# SDRAM.net
KiCad netlist of a schematic drawn in Altium Designer
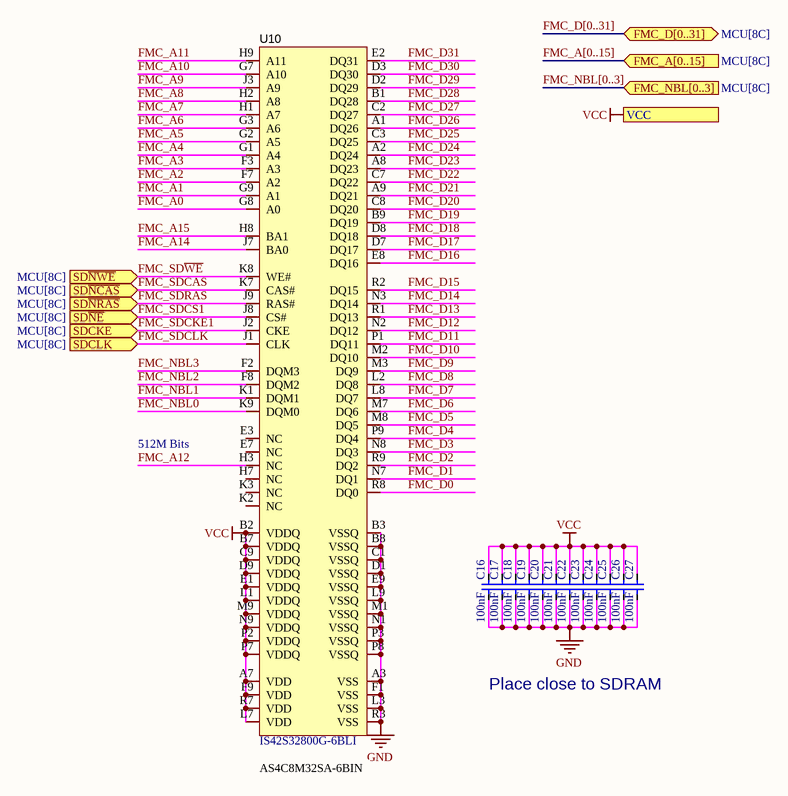
[diagram p0: SDRAM.SchDoc]

(export (version "E")
  (design (tool "Eeschema 10.0.6"))
  (components
    (comp (ref "C16")
      (value "100nF")
      (footprint "0402-C")
      (description "Capacitor")
      (libsource (lib "MyPcbLib") (part "电容-0402"))
    )
    (comp (ref "C17")
      (value "100nF")
      (footprint "0402-C")
      (description "Capacitor")
      (libsource (lib "MyPcbLib") (part "电容-0402"))
    )
    (comp (ref "C18")
      (value "100nF")
      (footprint "0402-C")
      (description "Capacitor")
      (libsource (lib "MyPcbLib") (part "电容-0402"))
    )
    (comp (ref "C19")
      (value "100nF")
      (footprint "0402-C")
      (description "Capacitor")
      (libsource (lib "MyPcbLib") (part "电容-0402"))
    )
    (comp (ref "C20")
      (value "100nF")
      (footprint "0402-C")
      (description "Capacitor")
      (libsource (lib "MyPcbLib") (part "电容-0402"))
    )
    (comp (ref "C21")
      (value "100nF")
      (footprint "0402-C")
      (description "Capacitor")
      (libsource (lib "MyPcbLib") (part "电容-0402"))
    )
    (comp (ref "C22")
      (value "100nF")
      (footprint "0402-C")
      (description "Capacitor")
      (libsource (lib "MyPcbLib") (part "电容-0402"))
    )
    (comp (ref "C23")
      (value "100nF")
      (footprint "0402-C")
      (description "Capacitor")
      (libsource (lib "MyPcbLib") (part "电容-0402"))
    )
    (comp (ref "C24")
      (value "100nF")
      (footprint "0402-C")
      (description "Capacitor")
      (libsource (lib "MyPcbLib") (part "电容-0402"))
    )
    (comp (ref "C25")
      (value "100nF")
      (footprint "0402-C")
      (description "Capacitor")
      (libsource (lib "MyPcbLib") (part "电容-0402"))
    )
    (comp (ref "C26")
      (value "100nF")
      (footprint "0402-C")
      (description "Capacitor")
      (libsource (lib "MyPcbLib") (part "电容-0402"))
    )
    (comp (ref "C27")
      (value "100nF")
      (footprint "0402-C")
      (description "Capacitor")
      (libsource (lib "MyPcbLib") (part "电容-0402"))
    )
    (comp (ref "U10")
      (value "IS42S32800G-6BLI")
      (footprint "BGA-90_L13.0-W8.0-R6-C15-P0.80-TL")
      (fields (field (name "MANUFACTURER") "ISSI(美国芯成)"))
      (libsource (lib "MyLib") (part "IS42S32800G-6BLI"))
    )
  )
  (nets
    (net (code "2") (name "/FMC_A0") (class "Default")
      (node (ref "U10") (pin "G8") (pinfunction "A0_G8") (pintype "passive"))
    )
    (net (code "3") (name "/FMC_A1") (class "Default")
      (node (ref "U10") (pin "G9") (pinfunction "A1_G9") (pintype "passive"))
    )
    (net (code "4") (name "/FMC_A2") (class "Default")
      (node (ref "U10") (pin "F7") (pinfunction "A2_F7") (pintype "passive"))
    )
    (net (code "5") (name "/FMC_A3") (class "Default")
      (node (ref "U10") (pin "F3") (pinfunction "A3_F3") (pintype "passive"))
    )
    (net (code "6") (name "/FMC_A4") (class "Default")
      (node (ref "U10") (pin "G1") (pinfunction "A4_G1") (pintype "passive"))
    )
    (net (code "7") (name "/FMC_A5") (class "Default")
      (node (ref "U10") (pin "G2") (pinfunction "A5_G2") (pintype "passive"))
    )
    (net (code "8") (name "/FMC_A6") (class "Default")
      (node (ref "U10") (pin "G3") (pinfunction "A6_G3") (pintype "passive"))
    )
    (net (code "9") (name "/FMC_A7") (class "Default")
      (node (ref "U10") (pin "H1") (pinfunction "A7_H1") (pintype "passive"))
    )
    (net (code "10") (name "/FMC_A8") (class "Default")
      (node (ref "U10") (pin "H2") (pinfunction "A8_H2") (pintype "passive"))
    )
    (net (code "11") (name "/FMC_A9") (class "Default")
      (node (ref "U10") (pin "J3") (pinfunction "A9_J3") (pintype "passive"))
    )
    (net (code "12") (name "/FMC_A10") (class "Default")
      (node (ref "U10") (pin "G7") (pinfunction "A10_G7") (pintype "passive"))
    )
    (net (code "13") (name "/FMC_A11") (class "Default")
      (node (ref "U10") (pin "H9") (pinfunction "A11_H9") (pintype "passive"))
    )
    (net (code "14") (name "/FMC_A12") (class "Default")
      (node (ref "U10") (pin "H3") (pinfunction "NC_H3") (pintype "passive"))
    )
    (net (code "15") (name "/FMC_A14") (class "Default")
      (node (ref "U10") (pin "J7") (pinfunction "BA0_J7") (pintype "passive"))
    )
    (net (code "16") (name "/FMC_A15") (class "Default")
      (node (ref "U10") (pin "H8") (pinfunction "BA1_H8") (pintype "passive"))
    )
    (net (code "18") (name "/FMC_D0") (class "Default")
      (node (ref "U10") (pin "R8") (pinfunction "DQ0_R8") (pintype "passive"))
    )
    (net (code "19") (name "/FMC_D1") (class "Default")
      (node (ref "U10") (pin "N7") (pinfunction "DQ1_N7") (pintype "passive"))
    )
    (net (code "20") (name "/FMC_D2") (class "Default")
      (node (ref "U10") (pin "R9") (pinfunction "DQ2_R9") (pintype "passive"))
    )
    (net (code "21") (name "/FMC_D3") (class "Default")
      (node (ref "U10") (pin "N8") (pinfunction "DQ3_N8") (pintype "passive"))
    )
    (net (code "22") (name "/FMC_D4") (class "Default")
      (node (ref "U10") (pin "P9") (pinfunction "DQ4_P9") (pintype "passive"))
    )
    (net (code "23") (name "/FMC_D5") (class "Default")
      (node (ref "U10") (pin "M8") (pinfunction "DQ5_M8") (pintype "passive"))
    )
    (net (code "24") (name "/FMC_D6") (class "Default")
      (node (ref "U10") (pin "M7") (pinfunction "DQ6_M7") (pintype "passive"))
    )
    (net (code "25") (name "/FMC_D7") (class "Default")
      (node (ref "U10") (pin "L8") (pinfunction "DQ7_L8") (pintype "passive"))
    )
    (net (code "26") (name "/FMC_D8") (class "Default")
      (node (ref "U10") (pin "L2") (pinfunction "DQ8_L2") (pintype "passive"))
    )
    (net (code "27") (name "/FMC_D9") (class "Default")
      (node (ref "U10") (pin "M3") (pinfunction "DQ9_M3") (pintype "passive"))
    )
    (net (code "28") (name "/FMC_D10") (class "Default")
      (node (ref "U10") (pin "M2") (pinfunction "DQ10_M2") (pintype "passive"))
    )
    (net (code "29") (name "/FMC_D11") (class "Default")
      (node (ref "U10") (pin "P1") (pinfunction "DQ11_P1") (pintype "passive"))
    )
    (net (code "30") (name "/FMC_D12") (class "Default")
      (node (ref "U10") (pin "N2") (pinfunction "DQ12_N2") (pintype "passive"))
    )
    (net (code "31") (name "/FMC_D13") (class "Default")
      (node (ref "U10") (pin "R1") (pinfunction "DQ13_R1") (pintype "passive"))
    )
    (net (code "32") (name "/FMC_D14") (class "Default")
      (node (ref "U10") (pin "N3") (pinfunction "DQ14_N3") (pintype "passive"))
    )
    (net (code "33") (name "/FMC_D15") (class "Default")
      (node (ref "U10") (pin "R2") (pinfunction "DQ15_R2") (pintype "passive"))
    )
    (net (code "34") (name "/FMC_D16") (class "Default")
      (node (ref "U10") (pin "E8") (pinfunction "DQ16_E8") (pintype "passive"))
    )
    (net (code "35") (name "/FMC_D17") (class "Default")
      (node (ref "U10") (pin "D7") (pinfunction "DQ17_D7") (pintype "passive"))
    )
    (net (code "36") (name "/FMC_D18") (class "Default")
      (node (ref "U10") (pin "D8") (pinfunction "DQ18_D8") (pintype "passive"))
    )
    (net (code "37") (name "/FMC_D19") (class "Default")
      (node (ref "U10") (pin "B9") (pinfunction "DQ19_B9") (pintype "passive"))
    )
    (net (code "38") (name "/FMC_D20") (class "Default")
      (node (ref "U10") (pin "C8") (pinfunction "DQ20_C8") (pintype "passive"))
    )
    (net (code "39") (name "/FMC_D21") (class "Default")
      (node (ref "U10") (pin "A9") (pinfunction "DQ21_A9") (pintype "passive"))
    )
    (net (code "40") (name "/FMC_D22") (class "Default")
      (node (ref "U10") (pin "C7") (pinfunction "DQ22_C7") (pintype "passive"))
    )
    (net (code "41") (name "/FMC_D23") (class "Default")
      (node (ref "U10") (pin "A8") (pinfunction "DQ23_A8") (pintype "passive"))
    )
    (net (code "42") (name "/FMC_D24") (class "Default")
      (node (ref "U10") (pin "A2") (pinfunction "DQ24_A2") (pintype "passive"))
    )
    (net (code "43") (name "/FMC_D25") (class "Default")
      (node (ref "U10") (pin "C3") (pinfunction "DQ25_C3") (pintype "passive"))
    )
    (net (code "44") (name "/FMC_D26") (class "Default")
      (node (ref "U10") (pin "A1") (pinfunction "DQ26_A1") (pintype "passive"))
    )
    (net (code "45") (name "/FMC_D27") (class "Default")
      (node (ref "U10") (pin "C2") (pinfunction "DQ27_C2") (pintype "passive"))
    )
    (net (code "46") (name "/FMC_D28") (class "Default")
      (node (ref "U10") (pin "B1") (pinfunction "DQ28_B1") (pintype "passive"))
    )
    (net (code "47") (name "/FMC_D29") (class "Default")
      (node (ref "U10") (pin "D2") (pinfunction "DQ29_D2") (pintype "passive"))
    )
    (net (code "48") (name "/FMC_D30") (class "Default")
      (node (ref "U10") (pin "D3") (pinfunction "DQ30_D3") (pintype "passive"))
    )
    (net (code "49") (name "/FMC_D31") (class "Default")
      (node (ref "U10") (pin "E2") (pinfunction "DQ31_E2") (pintype "passive"))
    )
    (net (code "51") (name "/FMC_NBL0") (class "Default")
      (node (ref "U10") (pin "K9") (pinfunction "DQM0_K9") (pintype "passive"))
    )
    (net (code "52") (name "/FMC_NBL1") (class "Default")
      (node (ref "U10") (pin "K1") (pinfunction "DQM1_K1") (pintype "passive"))
    )
    (net (code "53") (name "/FMC_NBL2") (class "Default")
      (node (ref "U10") (pin "F8") (pinfunction "DQM2_F8") (pintype "passive"))
    )
    (net (code "54") (name "/FMC_NBL3") (class "Default")
      (node (ref "U10") (pin "F2") (pinfunction "DQM3_F2") (pintype "passive"))
    )
    (net (code "56") (name "/FMC_SDCKE1") (class "Default")
      (node (ref "U10") (pin "J2") (pinfunction "CKE_J2") (pintype "passive"))
    )
    (net (code "57") (name "/FMC_SDCLK") (class "Default")
      (node (ref "U10") (pin "J1") (pinfunction "CLK_J1") (pintype "passive"))
    )
    (net (code "58") (name "/FMC_SD~{CAS}") (class "Default")
      (node (ref "U10") (pin "K7") (pinfunction "CAS#_K7") (pintype "passive"))
    )
    (net (code "59") (name "/FMC_SD~{CS}1") (class "Default")
      (node (ref "U10") (pin "J8") (pinfunction "CS#_J8") (pintype "passive"))
    )
    (net (code "60") (name "/FMC_SD~{RAS}") (class "Default")
      (node (ref "U10") (pin "J9") (pinfunction "RAS#_J9") (pintype "passive"))
    )
    (net (code "61") (name "/FMC_SD~{WE}") (class "Default")
      (node (ref "U10") (pin "K8") (pinfunction "WE#_K8") (pintype "passive"))
    )
    (net (code "62") (name "GND") (class "Default")
      (node (ref "C16") (pin "2") (pinfunction "2_2") (pintype "passive"))
      (node (ref "C17") (pin "2") (pinfunction "2_2") (pintype "passive"))
      (node (ref "C18") (pin "2") (pinfunction "2_2") (pintype "passive"))
      (node (ref "C19") (pin "2") (pinfunction "2_2") (pintype "passive"))
      (node (ref "C20") (pin "2") (pinfunction "2_2") (pintype "passive"))
      (node (ref "C21") (pin "2") (pinfunction "2_2") (pintype "passive"))
      (node (ref "C22") (pin "2") (pinfunction "2_2") (pintype "passive"))
      (node (ref "C23") (pin "2") (pinfunction "2_2") (pintype "passive"))
      (node (ref "C24") (pin "2") (pinfunction "2_2") (pintype "passive"))
      (node (ref "C25") (pin "2") (pinfunction "2_2") (pintype "passive"))
      (node (ref "C26") (pin "2") (pinfunction "2_2") (pintype "passive"))
      (node (ref "C27") (pin "2") (pinfunction "2_2") (pintype "passive"))
      (node (ref "U10") (pin "A3") (pinfunction "VSS_A3") (pintype "passive"))
      (node (ref "U10") (pin "B3") (pinfunction "VSSQ_B3") (pintype "passive"))
      (node (ref "U10") (pin "B8") (pinfunction "VSSQ_B8") (pintype "passive"))
      (node (ref "U10") (pin "C1") (pinfunction "VSSQ_C1") (pintype "passive"))
      (node (ref "U10") (pin "D1") (pinfunction "VSSQ_D1") (pintype "passive"))
      (node (ref "U10") (pin "E9") (pinfunction "VSSQ_E9") (pintype "passive"))
      (node (ref "U10") (pin "F1") (pinfunction "VSS_F1") (pintype "passive"))
      (node (ref "U10") (pin "L3") (pinfunction "VSS_L3") (pintype "passive"))
      (node (ref "U10") (pin "L9") (pinfunction "VSSQ_L9") (pintype "passive"))
      (node (ref "U10") (pin "M1") (pinfunction "VSSQ_M1") (pintype "passive"))
      (node (ref "U10") (pin "N1") (pinfunction "VSSQ_N1") (pintype "passive"))
      (node (ref "U10") (pin "P3") (pinfunction "VSSQ_P3") (pintype "passive"))
      (node (ref "U10") (pin "P8") (pinfunction "VSSQ_P8") (pintype "passive"))
      (node (ref "U10") (pin "R3") (pinfunction "VSS_R3") (pintype "passive"))
    )
    (net (code "63") (name "VCC") (class "Default")
      (node (ref "C16") (pin "1") (pinfunction "1_1") (pintype "passive"))
      (node (ref "C17") (pin "1") (pinfunction "1_1") (pintype "passive"))
      (node (ref "C18") (pin "1") (pinfunction "1_1") (pintype "passive"))
      (node (ref "C19") (pin "1") (pinfunction "1_1") (pintype "passive"))
      (node (ref "C20") (pin "1") (pinfunction "1_1") (pintype "passive"))
      (node (ref "C21") (pin "1") (pinfunction "1_1") (pintype "passive"))
      (node (ref "C22") (pin "1") (pinfunction "1_1") (pintype "passive"))
      (node (ref "C23") (pin "1") (pinfunction "1_1") (pintype "passive"))
      (node (ref "C24") (pin "1") (pinfunction "1_1") (pintype "passive"))
      (node (ref "C25") (pin "1") (pinfunction "1_1") (pintype "passive"))
      (node (ref "C26") (pin "1") (pinfunction "1_1") (pintype "passive"))
      (node (ref "C27") (pin "1") (pinfunction "1_1") (pintype "passive"))
      (node (ref "U10") (pin "A7") (pinfunction "VDD_A7") (pintype "passive"))
      (node (ref "U10") (pin "B2") (pinfunction "VDDQ_B2") (pintype "passive"))
      (node (ref "U10") (pin "B7") (pinfunction "VDDQ_B7") (pintype "passive"))
      (node (ref "U10") (pin "C9") (pinfunction "VDDQ_C9") (pintype "passive"))
      (node (ref "U10") (pin "D9") (pinfunction "VDDQ_D9") (pintype "passive"))
      (node (ref "U10") (pin "E1") (pinfunction "VDDQ_E1") (pintype "passive"))
      (node (ref "U10") (pin "F9") (pinfunction "VDD_F9") (pintype "passive"))
      (node (ref "U10") (pin "L1") (pinfunction "VDDQ_L1") (pintype "passive"))
      (node (ref "U10") (pin "L7") (pinfunction "VDD_L7") (pintype "passive"))
      (node (ref "U10") (pin "M9") (pinfunction "VDDQ_M9") (pintype "passive"))
      (node (ref "U10") (pin "N9") (pinfunction "VDDQ_N9") (pintype "passive"))
      (node (ref "U10") (pin "P2") (pinfunction "VDDQ_P2") (pintype "passive"))
      (node (ref "U10") (pin "P7") (pinfunction "VDDQ_P7") (pintype "passive"))
      (node (ref "U10") (pin "R7") (pinfunction "VDD_R7") (pintype "passive"))
    )
    (net (code "64") (name "unconnected-(U10-NC-PadE3)") (class "Default")
      (node (ref "U10") (pin "E3") (pinfunction "NC_E3") (pintype "passive"))
    )
    (net (code "65") (name "unconnected-(U10-NC-PadE7)") (class "Default")
      (node (ref "U10") (pin "E7") (pinfunction "NC_E7") (pintype "passive"))
    )
    (net (code "66") (name "unconnected-(U10-NC-PadH7)") (class "Default")
      (node (ref "U10") (pin "H7") (pinfunction "NC_H7") (pintype "passive"))
    )
    (net (code "67") (name "unconnected-(U10-NC-PadK2)") (class "Default")
      (node (ref "U10") (pin "K2") (pinfunction "NC_K2") (pintype "passive"))
    )
    (net (code "68") (name "unconnected-(U10-NC-PadK3)") (class "Default")
      (node (ref "U10") (pin "K3") (pinfunction "NC_K3") (pintype "passive"))
    )
  )
)
